# bluenumi.net
KiCad netlist of a schematic drawn in EAGLE
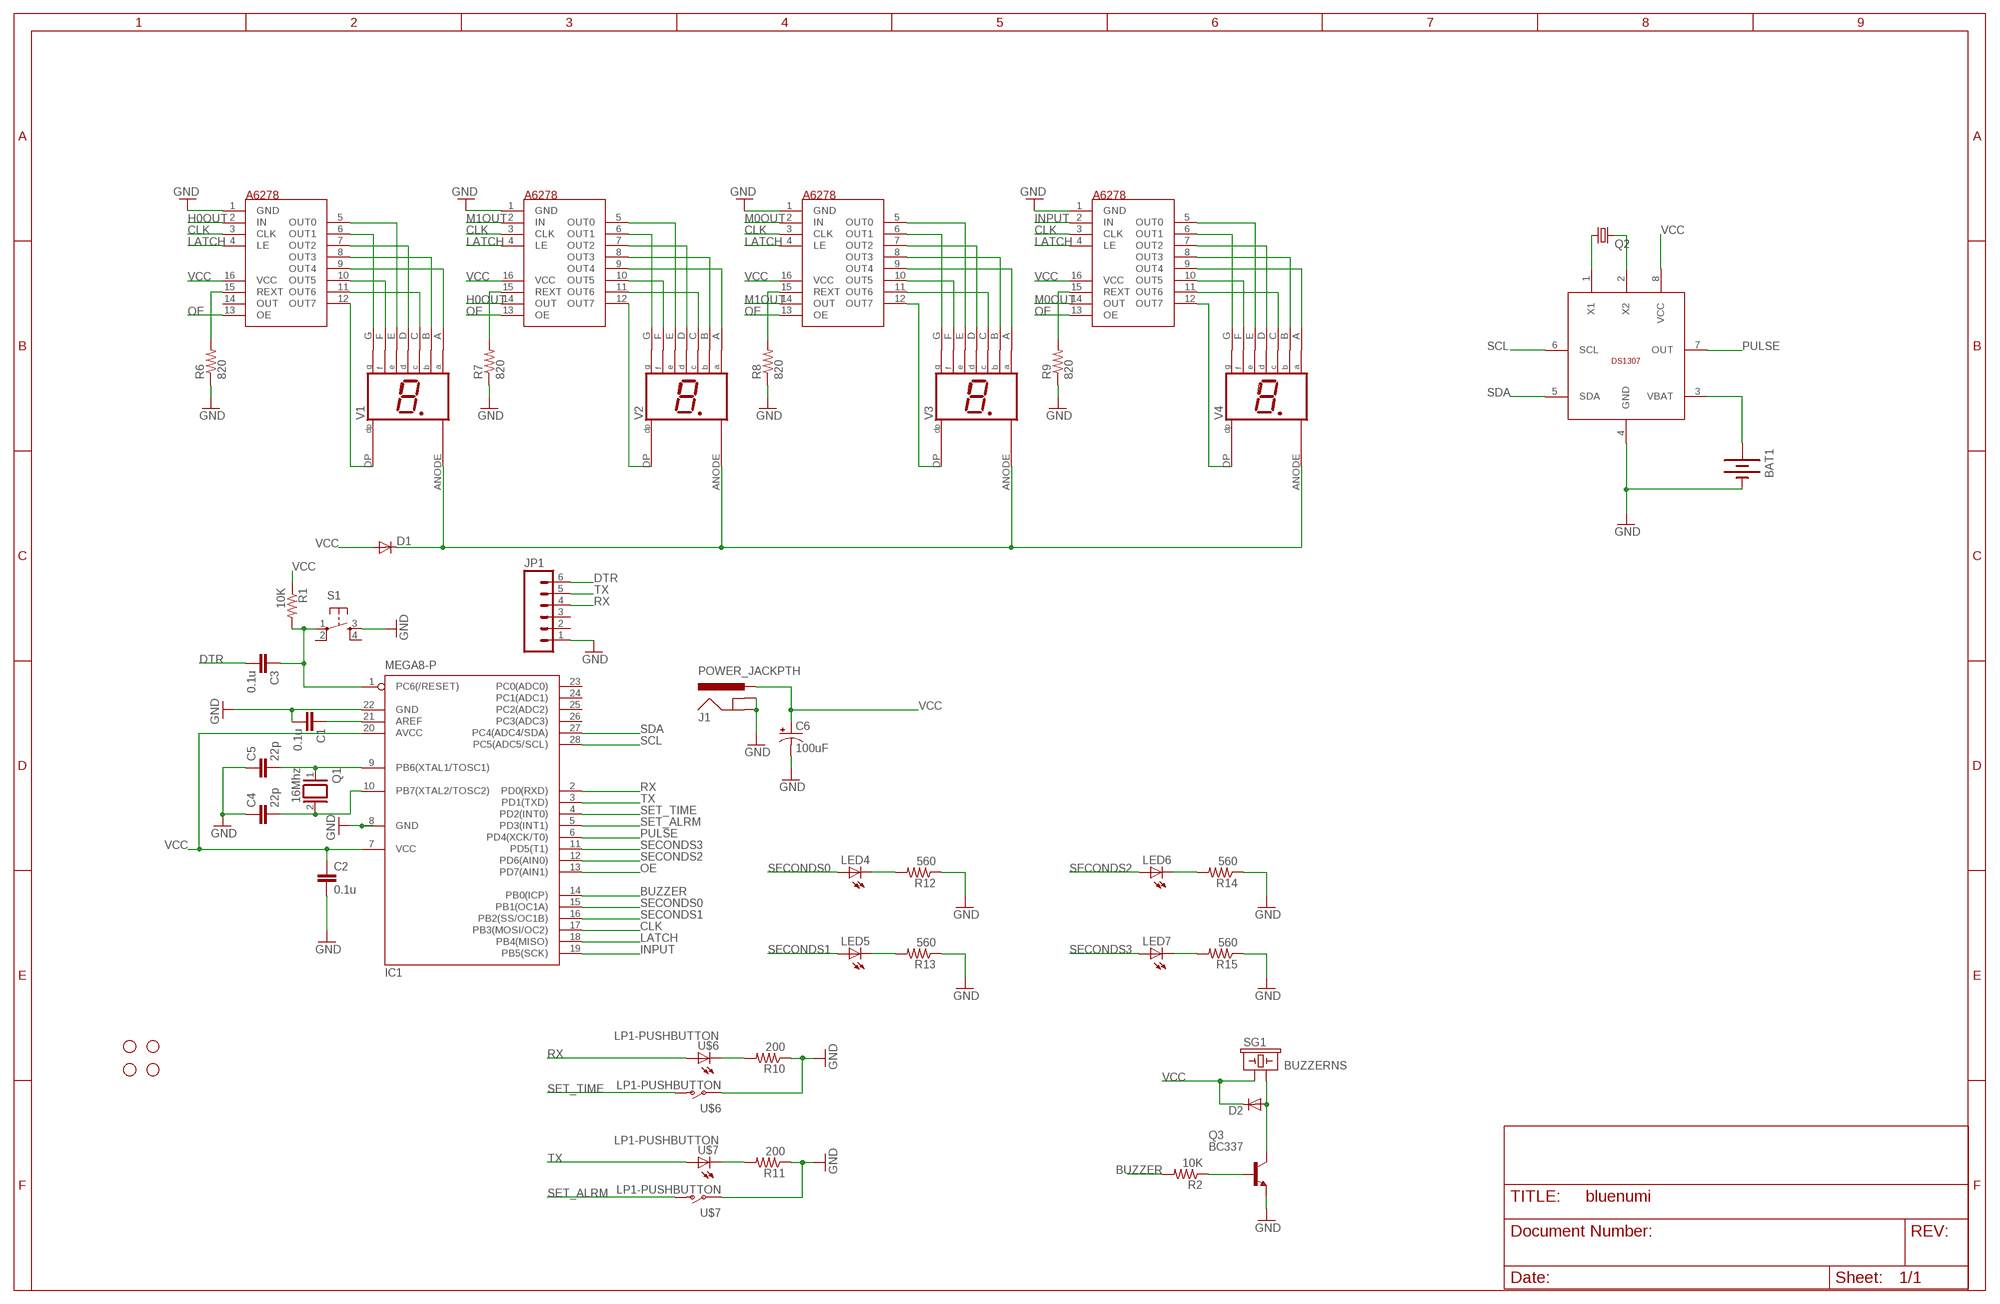
[diagram p0: schematic, sheet 1]

(export (version "E")
  (design (tool "Eeschema 10.0.6"))
  (components
    (comp (ref "BAT1")
      (value "BATTERY20PTH")
      (footprint "eagle-import:BATTCOM_20MM_PTH")
      (libsource (lib "eagle-import") (part "BATTERY20PTH"))
    )
    (comp (ref "C1")
      (value "0.1u")
      (footprint "eagle-import:CAP-PTH-SMALL")
      (libsource (lib "eagle-import") (part "CAPPTH"))
    )
    (comp (ref "C2")
      (value "0.1u")
      (footprint "eagle-import:CAP-PTH-SMALL")
      (libsource (lib "eagle-import") (part "CAPPTH"))
    )
    (comp (ref "C3")
      (value "0.1u")
      (footprint "eagle-import:CAP-PTH-SMALL")
      (libsource (lib "eagle-import") (part "CAPPTH"))
    )
    (comp (ref "C4")
      (value "22p")
      (footprint "eagle-import:CAP-PTH-SMALL")
      (libsource (lib "eagle-import") (part "CAPPTH"))
    )
    (comp (ref "C5")
      (value "22p")
      (footprint "eagle-import:CAP-PTH-SMALL")
      (libsource (lib "eagle-import") (part "CAPPTH"))
    )
    (comp (ref "C6")
      (value "100uF")
      (footprint "eagle-import:CPOL-RADIAL-10UF-25V")
      (libsource (lib "eagle-import") (part "CAP_POLPTH2"))
    )
    (comp (ref "D1")
      (value "DIODEPTH")
      (footprint "eagle-import:DIODE-1N4001")
      (libsource (lib "eagle-import") (part "DIODEPTH"))
    )
    (comp (ref "D2")
      (value "DIODEPTH")
      (footprint "eagle-import:DIODE-1N4001")
      (libsource (lib "eagle-import") (part "DIODEPTH"))
    )
    (comp (ref "IC1")
      (value "MEGA8-P")
      (footprint "eagle-import:DIL28-3")
      (libsource (lib "eagle-import") (part "MEGA8-P"))
    )
    (comp (ref "J1")
      (value "POWER_JACKPTH")
      (footprint "eagle-import:POWER_JACK_PTH")
      (libsource (lib "eagle-import") (part "POWER_JACKPTH"))
    )
    (comp (ref "JP1")
      (value "M06LOCK")
      (footprint "eagle-import:1X06_LOCK")
      (libsource (lib "eagle-import") (part "M06LOCK"))
    )
    (comp (ref "LED4")
      (value "LED5MM")
      (footprint "eagle-import:LED5MM")
      (libsource (lib "eagle-import") (part "LED5MM"))
    )
    (comp (ref "LED5")
      (value "LED5MM")
      (footprint "eagle-import:LED5MM")
      (libsource (lib "eagle-import") (part "LED5MM"))
    )
    (comp (ref "LED6")
      (value "LED5MM")
      (footprint "eagle-import:LED5MM")
      (libsource (lib "eagle-import") (part "LED5MM"))
    )
    (comp (ref "LED7")
      (value "LED5MM")
      (footprint "eagle-import:LED5MM")
      (libsource (lib "eagle-import") (part "LED5MM"))
    )
    (comp (ref "Q1")
      (value "16Mhz")
      (footprint "eagle-import:QS")
      (libsource (lib "eagle-import") (part "XTAL/S"))
    )
    (comp (ref "Q2")
      (value "CRYSTALTC26H")
      (footprint "eagle-import:TC26H")
      (libsource (lib "eagle-import") (part "CRYSTALTC26H"))
    )
    (comp (ref "Q3")
      (value "BC337")
      (footprint "eagle-import:TO92")
      (libsource (lib "eagle-import") (part "BC337"))
    )
    (comp (ref "R1")
      (value "10K")
      (footprint "eagle-import:AXIAL-0.3")
      (libsource (lib "eagle-import") (part "RESISTORPTH1"))
    )
    (comp (ref "R2")
      (value "10K")
      (footprint "eagle-import:AXIAL-0.3")
      (libsource (lib "eagle-import") (part "RESISTORPTH1"))
    )
    (comp (ref "R6")
      (value "820")
      (footprint "eagle-import:AXIAL-0.3")
      (libsource (lib "eagle-import") (part "RESISTORPTH1"))
    )
    (comp (ref "R7")
      (value "820")
      (footprint "eagle-import:AXIAL-0.3")
      (libsource (lib "eagle-import") (part "RESISTORPTH1"))
    )
    (comp (ref "R8")
      (value "820")
      (footprint "eagle-import:AXIAL-0.3")
      (libsource (lib "eagle-import") (part "RESISTORPTH1"))
    )
    (comp (ref "R9")
      (value "820")
      (footprint "eagle-import:AXIAL-0.3")
      (libsource (lib "eagle-import") (part "RESISTORPTH1"))
    )
    (comp (ref "R10")
      (value "200")
      (footprint "eagle-import:AXIAL-0.3")
      (libsource (lib "eagle-import") (part "RESISTORPTH1"))
    )
    (comp (ref "R11")
      (value "200")
      (footprint "eagle-import:AXIAL-0.3")
      (libsource (lib "eagle-import") (part "RESISTORPTH1"))
    )
    (comp (ref "R12")
      (value "560")
      (footprint "eagle-import:AXIAL-0.3")
      (libsource (lib "eagle-import") (part "RESISTORPTH1"))
    )
    (comp (ref "R13")
      (value "560")
      (footprint "eagle-import:AXIAL-0.3")
      (libsource (lib "eagle-import") (part "RESISTORPTH1"))
    )
    (comp (ref "R14")
      (value "560")
      (footprint "eagle-import:AXIAL-0.3")
      (libsource (lib "eagle-import") (part "RESISTORPTH1"))
    )
    (comp (ref "R15")
      (value "560")
      (footprint "eagle-import:AXIAL-0.3")
      (libsource (lib "eagle-import") (part "RESISTORPTH1"))
    )
    (comp (ref "S1")
      (value "TAC_SWITCHPTH")
      (footprint "eagle-import:TACTILE-PTH")
      (libsource (lib "eagle-import") (part "TAC_SWITCHPTH"))
    )
    (comp (ref "SG1")
      (value "BUZZERNS")
      (footprint "eagle-import:BUZZER-12MM-NS")
      (libsource (lib "eagle-import") (part "BUZZERNS"))
    )
    (comp (ref "U$1")
      (value "TLC5916")
      (footprint "eagle-import:DIL16")
      (libsource (lib "eagle-import") (part "A6278EAT"))
    )
    (comp (ref "U$2")
      (value "A6278EAT")
      (footprint "eagle-import:DIL16")
      (libsource (lib "eagle-import") (part "A6278EAT"))
    )
    (comp (ref "U$3")
      (value "A6278EAT")
      (footprint "eagle-import:DIL16")
      (libsource (lib "eagle-import") (part "A6278EAT"))
    )
    (comp (ref "U$4")
      (value "A6278EAT")
      (footprint "eagle-import:DIL16")
      (libsource (lib "eagle-import") (part "A6278EAT"))
    )
    (comp (ref "U$5")
      (value "DS1307")
      (footprint "eagle-import:DIL08")
      (libsource (lib "eagle-import") (part "DS1307"))
    )
    (comp (ref "U$6")
      (value "LP1-PUSHBUTTON")
      (footprint "eagle-import:LP1-PUSHBUTTON")
      (libsource (lib "eagle-import") (part "LP1-PUSHBUTTON"))
    )
    (comp (ref "U$7")
      (value "LP1-PUSHBUTTON")
      (footprint "eagle-import:LP1-PUSHBUTTON")
      (libsource (lib "eagle-import") (part "LP1-PUSHBUTTON"))
    )
    (comp (ref "U$8")
      (value "STAND-OFF")
      (footprint "eagle-import:STAND-OFF")
      (libsource (lib "eagle-import") (part "STAND-OFF"))
    )
    (comp (ref "U$9")
      (value "STAND-OFF")
      (footprint "eagle-import:STAND-OFF")
      (libsource (lib "eagle-import") (part "STAND-OFF"))
    )
    (comp (ref "U$10")
      (value "STAND-OFF")
      (footprint "eagle-import:STAND-OFF")
      (libsource (lib "eagle-import") (part "STAND-OFF"))
    )
    (comp (ref "U$11")
      (value "STAND-OFF")
      (footprint "eagle-import:STAND-OFF")
      (libsource (lib "eagle-import") (part "STAND-OFF"))
    )
    (comp (ref "V1")
      (value "IV-9-UNDERLIT")
      (footprint "eagle-import:9PINTUBE-WIDE")
      (libsource (lib "eagle-import") (part "IV-9-UNDERLIT"))
    )
    (comp (ref "V2")
      (value "IV-9-UNDERLIT")
      (footprint "eagle-import:9PINTUBE-WIDE")
      (libsource (lib "eagle-import") (part "IV-9-UNDERLIT"))
    )
    (comp (ref "V3")
      (value "IV-9-UNDERLIT")
      (footprint "eagle-import:9PINTUBE-WIDE")
      (libsource (lib "eagle-import") (part "IV-9-UNDERLIT"))
    )
    (comp (ref "V4")
      (value "IV-9-UNDERLIT")
      (footprint "eagle-import:9PINTUBE-WIDE")
      (libsource (lib "eagle-import") (part "IV-9-UNDERLIT"))
    )
  )
  (nets
    (net (code "1") (name "/BUZZER") (class "Default")
      (node (ref "IC1") (pin "14") (pinfunction "PB0(ICP)_14") (pintype "bidirectional"))
      (node (ref "R2") (pin "P$2") (pinfunction "2_P$2") (pintype "passive"))
    )
    (net (code "2") (name "/CLK") (class "Default")
      (node (ref "IC1") (pin "17") (pinfunction "PB3(MOSI/OC2)_17") (pintype "bidirectional"))
      (node (ref "U$1") (pin "3") (pinfunction "CLK_3") (pintype "bidirectional"))
      (node (ref "U$2") (pin "3") (pinfunction "CLK_3") (pintype "bidirectional"))
      (node (ref "U$3") (pin "3") (pinfunction "CLK_3") (pintype "bidirectional"))
      (node (ref "U$4") (pin "3") (pinfunction "CLK_3") (pintype "bidirectional"))
    )
    (net (code "3") (name "/DTR") (class "Default")
      (node (ref "C3") (pin "2") (pinfunction "2_2") (pintype "passive"))
      (node (ref "JP1") (pin "6") (pinfunction "6_6") (pintype "passive"))
    )
    (net (code "4") (name "/H0OUT") (class "Default")
      (node (ref "U$1") (pin "2") (pinfunction "IN_2") (pintype "bidirectional"))
      (node (ref "U$2") (pin "14") (pinfunction "OUT_14") (pintype "bidirectional"))
    )
    (net (code "5") (name "/INPUT") (class "Default")
      (node (ref "IC1") (pin "19") (pinfunction "PB5(SCK)_19") (pintype "bidirectional"))
      (node (ref "U$4") (pin "2") (pinfunction "IN_2") (pintype "bidirectional"))
    )
    (net (code "6") (name "/LATCH") (class "Default")
      (node (ref "IC1") (pin "18") (pinfunction "PB4(MISO)_18") (pintype "bidirectional"))
      (node (ref "U$1") (pin "4") (pinfunction "LE_4") (pintype "bidirectional"))
      (node (ref "U$2") (pin "4") (pinfunction "LE_4") (pintype "bidirectional"))
      (node (ref "U$3") (pin "4") (pinfunction "LE_4") (pintype "bidirectional"))
      (node (ref "U$4") (pin "4") (pinfunction "LE_4") (pintype "bidirectional"))
    )
    (net (code "7") (name "/M0OUT") (class "Default")
      (node (ref "U$3") (pin "2") (pinfunction "IN_2") (pintype "bidirectional"))
      (node (ref "U$4") (pin "14") (pinfunction "OUT_14") (pintype "bidirectional"))
    )
    (net (code "8") (name "/M1OUT") (class "Default")
      (node (ref "U$2") (pin "2") (pinfunction "IN_2") (pintype "bidirectional"))
      (node (ref "U$3") (pin "14") (pinfunction "OUT_14") (pintype "bidirectional"))
    )
    (net (code "9") (name "/OE") (class "Default")
      (node (ref "IC1") (pin "13") (pinfunction "PD7(AIN1)_13") (pintype "bidirectional"))
      (node (ref "U$1") (pin "13") (pinfunction "OE_13") (pintype "bidirectional"))
      (node (ref "U$2") (pin "13") (pinfunction "OE_13") (pintype "bidirectional"))
      (node (ref "U$3") (pin "13") (pinfunction "OE_13") (pintype "bidirectional"))
      (node (ref "U$4") (pin "13") (pinfunction "OE_13") (pintype "bidirectional"))
    )
    (net (code "10") (name "/PULSE") (class "Default")
      (node (ref "IC1") (pin "6") (pinfunction "PD4(XCK/T0)_6") (pintype "bidirectional"))
      (node (ref "U$5") (pin "7") (pinfunction "OUT_7") (pintype "bidirectional"))
    )
    (net (code "11") (name "/RX") (class "Default")
      (node (ref "IC1") (pin "2") (pinfunction "PD0(RXD)_2") (pintype "bidirectional"))
      (node (ref "JP1") (pin "4") (pinfunction "4_4") (pintype "passive"))
      (node (ref "U$6") (pin "ANODE") (pinfunction "ANODE_ANODE") (pintype "passive"))
    )
    (net (code "12") (name "/SCL") (class "Default")
      (node (ref "IC1") (pin "28") (pinfunction "PC5(ADC5/SCL)_28") (pintype "bidirectional"))
      (node (ref "U$5") (pin "6") (pinfunction "SCL_6") (pintype "bidirectional"))
    )
    (net (code "13") (name "/SDA") (class "Default")
      (node (ref "IC1") (pin "27") (pinfunction "PC4(ADC4/SDA)_27") (pintype "bidirectional"))
      (node (ref "U$5") (pin "5") (pinfunction "SDA_5") (pintype "bidirectional"))
    )
    (net (code "14") (name "/SECONDS0") (class "Default")
      (node (ref "IC1") (pin "15") (pinfunction "PB1(OC1A)_15") (pintype "bidirectional"))
      (node (ref "LED4") (pin "A") (pinfunction "A_A") (pintype "passive"))
    )
    (net (code "15") (name "/SECONDS1") (class "Default")
      (node (ref "IC1") (pin "16") (pinfunction "PB2(SS/OC1B)_16") (pintype "bidirectional"))
      (node (ref "LED5") (pin "A") (pinfunction "A_A") (pintype "passive"))
    )
    (net (code "16") (name "/SECONDS2") (class "Default")
      (node (ref "IC1") (pin "12") (pinfunction "PD6(AIN0)_12") (pintype "bidirectional"))
      (node (ref "LED6") (pin "A") (pinfunction "A_A") (pintype "passive"))
    )
    (net (code "17") (name "/SECONDS3") (class "Default")
      (node (ref "IC1") (pin "11") (pinfunction "PD5(T1)_11") (pintype "bidirectional"))
      (node (ref "LED7") (pin "A") (pinfunction "A_A") (pintype "passive"))
    )
    (net (code "18") (name "/SET_ALRM") (class "Default")
      (node (ref "IC1") (pin "5") (pinfunction "PD3(INT1)_5") (pintype "bidirectional"))
      (node (ref "U$7") (pin "S1") (pinfunction "S1_S1") (pintype "passive"))
    )
    (net (code "19") (name "/SET_TIME") (class "Default")
      (node (ref "IC1") (pin "4") (pinfunction "PD2(INT0)_4") (pintype "bidirectional"))
      (node (ref "U$6") (pin "S1") (pinfunction "S1_S1") (pintype "passive"))
    )
    (net (code "20") (name "/TX") (class "Default")
      (node (ref "IC1") (pin "3") (pinfunction "PD1(TXD)_3") (pintype "bidirectional"))
      (node (ref "JP1") (pin "5") (pinfunction "5_5") (pintype "passive"))
      (node (ref "U$7") (pin "ANODE") (pinfunction "ANODE_ANODE") (pintype "passive"))
    )
    (net (code "21") (name "/VCC") (class "Default")
      (node (ref "C2") (pin "1") (pinfunction "1_1") (pintype "passive"))
      (node (ref "C6") (pin "1") (pinfunction "+_1") (pintype "passive"))
      (node (ref "D1") (pin "A") (pinfunction "A_A") (pintype "passive"))
      (node (ref "D2") (pin "C") (pinfunction "C_C") (pintype "passive"))
      (node (ref "IC1") (pin "20") (pinfunction "AVCC_20") (pintype "power_in"))
      (node (ref "IC1") (pin "7") (pinfunction "VCC_7") (pintype "power_in"))
      (node (ref "J1") (pin "PWR") (pinfunction "PWR_PWR") (pintype "bidirectional"))
      (node (ref "R1") (pin "P$1") (pinfunction "1_P$1") (pintype "passive"))
      (node (ref "SG1") (pin "+") (pinfunction "1_+") (pintype "passive"))
      (node (ref "U$1") (pin "16") (pinfunction "VCC_16") (pintype "bidirectional"))
      (node (ref "U$2") (pin "16") (pinfunction "VCC_16") (pintype "bidirectional"))
      (node (ref "U$3") (pin "16") (pinfunction "VCC_16") (pintype "bidirectional"))
      (node (ref "U$4") (pin "16") (pinfunction "VCC_16") (pintype "bidirectional"))
      (node (ref "U$5") (pin "8") (pinfunction "VCC_8") (pintype "bidirectional"))
    )
    (net (code "22") (name "GND") (class "Default")
      (node (ref "BAT1") (pin "2") (pinfunction "-_2") (pintype "power_in"))
      (node (ref "C1") (pin "2") (pinfunction "2_2") (pintype "passive"))
      (node (ref "C2") (pin "2") (pinfunction "2_2") (pintype "passive"))
      (node (ref "C4") (pin "1") (pinfunction "1_1") (pintype "passive"))
      (node (ref "C5") (pin "1") (pinfunction "1_1") (pintype "passive"))
      (node (ref "C6") (pin "2") (pinfunction "-_2") (pintype "passive"))
      (node (ref "IC1") (pin "22") (pinfunction "GND_22") (pintype "power_in"))
      (node (ref "IC1") (pin "8") (pinfunction "GND_8") (pintype "power_in"))
      (node (ref "J1") (pin "GND") (pinfunction "GND_GND") (pintype "bidirectional"))
      (node (ref "J1") (pin "GNDBREAK") (pinfunction "GNDBREAK_GNDBREAK") (pintype "bidirectional"))
      (node (ref "JP1") (pin "1") (pinfunction "1_1") (pintype "passive"))
      (node (ref "Q3") (pin "1") (pinfunction "E_1") (pintype "passive"))
      (node (ref "R10") (pin "P$1") (pinfunction "1_P$1") (pintype "passive"))
      (node (ref "R11") (pin "P$1") (pinfunction "1_P$1") (pintype "passive"))
      (node (ref "R12") (pin "P$1") (pinfunction "1_P$1") (pintype "passive"))
      (node (ref "R13") (pin "P$1") (pinfunction "1_P$1") (pintype "passive"))
      (node (ref "R14") (pin "P$1") (pinfunction "1_P$1") (pintype "passive"))
      (node (ref "R15") (pin "P$1") (pinfunction "1_P$1") (pintype "passive"))
      (node (ref "R6") (pin "P$1") (pinfunction "1_P$1") (pintype "passive"))
      (node (ref "R7") (pin "P$1") (pinfunction "1_P$1") (pintype "passive"))
      (node (ref "R8") (pin "P$1") (pinfunction "1_P$1") (pintype "passive"))
      (node (ref "R9") (pin "P$1") (pinfunction "1_P$1") (pintype "passive"))
      (node (ref "S1") (pin "3") (pinfunction "3_3") (pintype "passive"))
      (node (ref "U$1") (pin "1") (pinfunction "GND_1") (pintype "bidirectional"))
      (node (ref "U$2") (pin "1") (pinfunction "GND_1") (pintype "bidirectional"))
      (node (ref "U$3") (pin "1") (pinfunction "GND_1") (pintype "bidirectional"))
      (node (ref "U$4") (pin "1") (pinfunction "GND_1") (pintype "bidirectional"))
      (node (ref "U$5") (pin "4") (pinfunction "GND_4") (pintype "bidirectional"))
      (node (ref "U$6") (pin "S2") (pinfunction "S2_S2") (pintype "passive"))
      (node (ref "U$7") (pin "S2") (pinfunction "S2_S2") (pintype "passive"))
    )
    (net (code "23") (name "Net-(BAT1-+)") (class "Default")
      (node (ref "BAT1") (pin "1") (pinfunction "+_1") (pintype "power_in"))
      (node (ref "U$5") (pin "3") (pinfunction "VBAT_3") (pintype "bidirectional"))
    )
    (net (code "24") (name "Net-(D1-PadC)") (class "Default")
      (node (ref "D1") (pin "C") (pinfunction "C_C") (pintype "passive"))
      (node (ref "V1") (pin "ANODE") (pinfunction "ANODE_ANODE") (pintype "passive"))
      (node (ref "V2") (pin "ANODE") (pinfunction "ANODE_ANODE") (pintype "passive"))
      (node (ref "V3") (pin "ANODE") (pinfunction "ANODE_ANODE") (pintype "passive"))
      (node (ref "V4") (pin "ANODE") (pinfunction "ANODE_ANODE") (pintype "passive"))
    )
    (net (code "25") (name "Net-(IC1-AREF)") (class "Default")
      (node (ref "C1") (pin "1") (pinfunction "1_1") (pintype "passive"))
      (node (ref "IC1") (pin "21") (pinfunction "AREF_21") (pintype "passive"))
    )
    (net (code "26") (name "Net-(IC1-PB6(XTAL1{slash}TOSC1))") (class "Default")
      (node (ref "C5") (pin "2") (pinfunction "2_2") (pintype "passive"))
      (node (ref "IC1") (pin "9") (pinfunction "PB6(XTAL1/TOSC1)_9") (pintype "bidirectional"))
      (node (ref "Q1") (pin "1") (pinfunction "1_1") (pintype "passive"))
    )
    (net (code "27") (name "Net-(IC1-PB7(XTAL2{slash}TOSC2))") (class "Default")
      (node (ref "C4") (pin "2") (pinfunction "2_2") (pintype "passive"))
      (node (ref "IC1") (pin "10") (pinfunction "PB7(XTAL2/TOSC2)_10") (pintype "bidirectional"))
      (node (ref "Q1") (pin "2") (pinfunction "2_2") (pintype "passive"))
    )
    (net (code "28") (name "Net-(IC1-PC6({slash}RESET))") (class "Default")
      (node (ref "C3") (pin "1") (pinfunction "1_1") (pintype "passive"))
      (node (ref "IC1") (pin "1") (pinfunction "PC6(/RESET)_1") (pintype "bidirectional"))
      (node (ref "R1") (pin "P$2") (pinfunction "2_P$2") (pintype "passive"))
      (node (ref "S1") (pin "1") (pinfunction "1_1") (pintype "passive"))
    )
    (net (code "29") (name "Net-(LED4-C)") (class "Default")
      (node (ref "LED4") (pin "K") (pinfunction "C_K") (pintype "passive"))
      (node (ref "R12") (pin "P$2") (pinfunction "2_P$2") (pintype "passive"))
    )
    (net (code "30") (name "Net-(LED5-C)") (class "Default")
      (node (ref "LED5") (pin "K") (pinfunction "C_K") (pintype "passive"))
      (node (ref "R13") (pin "P$2") (pinfunction "2_P$2") (pintype "passive"))
    )
    (net (code "31") (name "Net-(LED6-C)") (class "Default")
      (node (ref "LED6") (pin "K") (pinfunction "C_K") (pintype "passive"))
      (node (ref "R14") (pin "P$2") (pinfunction "2_P$2") (pintype "passive"))
    )
    (net (code "32") (name "Net-(LED7-C)") (class "Default")
      (node (ref "LED7") (pin "K") (pinfunction "C_K") (pintype "passive"))
      (node (ref "R15") (pin "P$2") (pinfunction "2_P$2") (pintype "passive"))
    )
    (net (code "33") (name "Net-(Q3-B)") (class "Default")
      (node (ref "Q3") (pin "2") (pinfunction "B_2") (pintype "passive"))
      (node (ref "R2") (pin "P$1") (pinfunction "1_P$1") (pintype "passive"))
    )
    (net (code "34") (name "Net-(Q3-C)") (class "Default")
      (node (ref "D2") (pin "A") (pinfunction "A_A") (pintype "passive"))
      (node (ref "Q3") (pin "3") (pinfunction "C_3") (pintype "passive"))
      (node (ref "SG1") (pin "-") (pinfunction "2_-") (pintype "passive"))
    )
    (net (code "35") (name "Net-(R6-2)") (class "Default")
      (node (ref "R6") (pin "P$2") (pinfunction "2_P$2") (pintype "passive"))
      (node (ref "U$1") (pin "15") (pinfunction "REXT_15") (pintype "bidirectional"))
    )
    (net (code "36") (name "Net-(R7-2)") (class "Default")
      (node (ref "R7") (pin "P$2") (pinfunction "2_P$2") (pintype "passive"))
      (node (ref "U$2") (pin "15") (pinfunction "REXT_15") (pintype "bidirectional"))
    )
    (net (code "37") (name "Net-(R8-2)") (class "Default")
      (node (ref "R8") (pin "P$2") (pinfunction "2_P$2") (pintype "passive"))
      (node (ref "U$3") (pin "15") (pinfunction "REXT_15") (pintype "bidirectional"))
    )
    (net (code "38") (name "Net-(R9-2)") (class "Default")
      (node (ref "R9") (pin "P$2") (pinfunction "2_P$2") (pintype "passive"))
      (node (ref "U$4") (pin "15") (pinfunction "REXT_15") (pintype "bidirectional"))
    )
    (net (code "39") (name "Net-(R10-2)") (class "Default")
      (node (ref "R10") (pin "P$2") (pinfunction "2_P$2") (pintype "passive"))
      (node (ref "U$6") (pin "CATHODE") (pinfunction "CATHODE_CATHODE") (pintype "passive"))
    )
    (net (code "40") (name "Net-(R11-2)") (class "Default")
      (node (ref "R11") (pin "P$2") (pinfunction "2_P$2") (pintype "passive"))
      (node (ref "U$7") (pin "CATHODE") (pinfunction "CATHODE_CATHODE") (pintype "passive"))
    )
    (net (code "41") (name "Net-(U$1-OUT0)") (class "Default")
      (node (ref "U$1") (pin "5") (pinfunction "OUT0_5") (pintype "bidirectional"))
      (node (ref "V1") (pin "E") (pinfunction "E_E") (pintype "passive"))
    )
    (net (code "42") (name "Net-(U$1-OUT1)") (class "Default")
      (node (ref "U$1") (pin "6") (pinfunction "OUT1_6") (pintype "bidirectional"))
      (node (ref "V1") (pin "G") (pinfunction "G_G") (pintype "passive"))
    )
    (net (code "43") (name "Net-(U$1-OUT2)") (class "Default")
      (node (ref "U$1") (pin "7") (pinfunction "OUT2_7") (pintype "bidirectional"))
      (node (ref "V1") (pin "D") (pinfunction "D_D") (pintype "passive"))
    )
    (net (code "44") (name "Net-(U$1-OUT3)") (class "Default")
      (node (ref "U$1") (pin "8") (pinfunction "OUT3_8") (pintype "bidirectional"))
      (node (ref "V1") (pin "B") (pinfunction "B_B") (pintype "passive"))
    )
    (net (code "45") (name "Net-(U$1-OUT4)") (class "Default")
      (node (ref "U$1") (pin "9") (pinfunction "OUT4_9") (pintype "bidirectional"))
      (node (ref "V1") (pin "A") (pinfunction "A_A") (pintype "passive"))
    )
    (net (code "46") (name "Net-(U$1-OUT5)") (class "Default")
      (node (ref "U$1") (pin "10") (pinfunction "OUT5_10") (pintype "bidirectional"))
      (node (ref "V1") (pin "F") (pinfunction "F_F") (pintype "passive"))
    )
    (net (code "47") (name "Net-(U$1-OUT6)") (class "Default")
      (node (ref "U$1") (pin "11") (pinfunction "OUT6_11") (pintype "bidirectional"))
      (node (ref "V1") (pin "C") (pinfunction "C_C") (pintype "passive"))
    )
    (net (code "48") (name "Net-(U$1-OUT7)") (class "Default")
      (node (ref "U$1") (pin "12") (pinfunction "OUT7_12") (pintype "bidirectional"))
      (node (ref "V1") (pin "DP") (pinfunction "DP_DP") (pintype "passive"))
    )
    (net (code "49") (name "Net-(U$2-OUT0)") (class "Default")
      (node (ref "U$2") (pin "5") (pinfunction "OUT0_5") (pintype "bidirectional"))
      (node (ref "V2") (pin "E") (pinfunction "E_E") (pintype "passive"))
    )
    (net (code "50") (name "Net-(U$2-OUT1)") (class "Default")
      (node (ref "U$2") (pin "6") (pinfunction "OUT1_6") (pintype "bidirectional"))
      (node (ref "V2") (pin "G") (pinfunction "G_G") (pintype "passive"))
    )
    (net (code "51") (name "Net-(U$2-OUT2)") (class "Default")
      (node (ref "U$2") (pin "7") (pinfunction "OUT2_7") (pintype "bidirectional"))
      (node (ref "V2") (pin "D") (pinfunction "D_D") (pintype "passive"))
    )
    (net (code "52") (name "Net-(U$2-OUT3)") (class "Default")
      (node (ref "U$2") (pin "8") (pinfunction "OUT3_8") (pintype "bidirectional"))
      (node (ref "V2") (pin "B") (pinfunction "B_B") (pintype "passive"))
    )
    (net (code "53") (name "Net-(U$2-OUT4)") (class "Default")
      (node (ref "U$2") (pin "9") (pinfunction "OUT4_9") (pintype "bidirectional"))
      (node (ref "V2") (pin "A") (pinfunction "A_A") (pintype "passive"))
    )
    (net (code "54") (name "Net-(U$2-OUT5)") (class "Default")
      (node (ref "U$2") (pin "10") (pinfunction "OUT5_10") (pintype "bidirectional"))
      (node (ref "V2") (pin "F") (pinfunction "F_F") (pintype "passive"))
    )
    (net (code "55") (name "Net-(U$2-OUT6)") (class "Default")
      (node (ref "U$2") (pin "11") (pinfunction "OUT6_11") (pintype "bidirectional"))
      (node (ref "V2") (pin "C") (pinfunction "C_C") (pintype "passive"))
    )
    (net (code "56") (name "Net-(U$2-OUT7)") (class "Default")
      (node (ref "U$2") (pin "12") (pinfunction "OUT7_12") (pintype "bidirectional"))
      (node (ref "V2") (pin "DP") (pinfunction "DP_DP") (pintype "passive"))
    )
    (net (code "57") (name "Net-(U$3-OUT0)") (class "Default")
      (node (ref "U$3") (pin "5") (pinfunction "OUT0_5") (pintype "bidirectional"))
      (node (ref "V3") (pin "E") (pinfunction "E_E") (pintype "passive"))
    )
    (net (code "58") (name "Net-(U$3-OUT1)") (class "Default")
      (node (ref "U$3") (pin "6") (pinfunction "OUT1_6") (pintype "bidirectional"))
      (node (ref "V3") (pin "G") (pinfunction "G_G") (pintype "passive"))
    )
    (net (code "59") (name "Net-(U$3-OUT2)") (class "Default")
      (node (ref "U$3") (pin "7") (pinfunction "OUT2_7") (pintype "bidirectional"))
      (node (ref "V3") (pin "D") (pinfunction "D_D") (pintype "passive"))
    )
    (net (code "60") (name "Net-(U$3-OUT3)") (class "Default")
      (node (ref "U$3") (pin "8") (pinfunction "OUT3_8") (pintype "bidirectional"))
      (node (ref "V3") (pin "B") (pinfunction "B_B") (pintype "passive"))
    )
    (net (code "61") (name "Net-(U$3-OUT4)") (class "Default")
      (node (ref "U$3") (pin "9") (pinfunction "OUT4_9") (pintype "bidirectional"))
      (node (ref "V3") (pin "A") (pinfunction "A_A") (pintype "passive"))
    )
    (net (code "62") (name "Net-(U$3-OUT5)") (class "Default")
      (node (ref "U$3") (pin "10") (pinfunction "OUT5_10") (pintype "bidirectional"))
      (node (ref "V3") (pin "F") (pinfunction "F_F") (pintype "passive"))
    )
    (net (code "63") (name "Net-(U$3-OUT6)") (class "Default")
      (node (ref "U$3") (pin "11") (pinfunction "OUT6_11") (pintype "bidirectional"))
      (node (ref "V3") (pin "C") (pinfunction "C_C") (pintype "passive"))
    )
    (net (code "64") (name "Net-(U$3-OUT7)") (class "Default")
      (node (ref "U$3") (pin "12") (pinfunction "OUT7_12") (pintype "bidirectional"))
      (node (ref "V3") (pin "DP") (pinfunction "DP_DP") (pintype "passive"))
    )
    (net (code "65") (name "Net-(U$4-OUT0)") (class "Default")
      (node (ref "U$4") (pin "5") (pinfunction "OUT0_5") (pintype "bidirectional"))
      (node (ref "V4") (pin "E") (pinfunction "E_E") (pintype "passive"))
    )
    (net (code "66") (name "Net-(U$4-OUT1)") (class "Default")
      (node (ref "U$4") (pin "6") (pinfunction "OUT1_6") (pintype "bidirectional"))
      (node (ref "V4") (pin "G") (pinfunction "G_G") (pintype "passive"))
    )
    (net (code "67") (name "Net-(U$4-OUT2)") (class "Default")
      (node (ref "U$4") (pin "7") (pinfunction "OUT2_7") (pintype "bidirectional"))
      (node (ref "V4") (pin "D") (pinfunction "D_D") (pintype "passive"))
    )
    (net (code "68") (name "Net-(U$4-OUT3)") (class "Default")
      (node (ref "U$4") (pin "8") (pinfunction "OUT3_8") (pintype "bidirectional"))
      (node (ref "V4") (pin "B") (pinfunction "B_B") (pintype "passive"))
    )
    (net (code "69") (name "Net-(U$4-OUT4)") (class "Default")
      (node (ref "U$4") (pin "9") (pinfunction "OUT4_9") (pintype "bidirectional"))
      (node (ref "V4") (pin "A") (pinfunction "A_A") (pintype "passive"))
    )
    (net (code "70") (name "Net-(U$4-OUT5)") (class "Default")
      (node (ref "U$4") (pin "10") (pinfunction "OUT5_10") (pintype "bidirectional"))
      (node (ref "V4") (pin "F") (pinfunction "F_F") (pintype "passive"))
    )
    (net (code "71") (name "Net-(U$4-OUT6)") (class "Default")
      (node (ref "U$4") (pin "11") (pinfunction "OUT6_11") (pintype "bidirectional"))
      (node (ref "V4") (pin "C") (pinfunction "C_C") (pintype "passive"))
    )
    (net (code "72") (name "Net-(U$4-OUT7)") (class "Default")
      (node (ref "U$4") (pin "12") (pinfunction "OUT7_12") (pintype "bidirectional"))
      (node (ref "V4") (pin "DP") (pinfunction "DP_DP") (pintype "passive"))
    )
    (net (code "73") (name "Net-(U$5-X1)") (class "Default")
      (node (ref "Q2") (pin "1") (pinfunction "1_1") (pintype "passive"))
      (node (ref "U$5") (pin "1") (pinfunction "X1_1") (pintype "bidirectional"))
    )
    (net (code "74") (name "Net-(U$5-X2)") (class "Default")
      (node (ref "Q2") (pin "2") (pinfunction "2_2") (pintype "passive"))
      (node (ref "U$5") (pin "2") (pinfunction "X2_2") (pintype "bidirectional"))
    )
    (net (code "75") (name "unconnected-(IC1-PC0(ADC0)-Pad23)") (class "Default")
      (node (ref "IC1") (pin "23") (pinfunction "PC0(ADC0)_23") (pintype "bidirectional"))
    )
    (net (code "76") (name "unconnected-(IC1-PC1(ADC1)-Pad24)") (class "Default")
      (node (ref "IC1") (pin "24") (pinfunction "PC1(ADC1)_24") (pintype "bidirectional"))
    )
    (net (code "77") (name "unconnected-(IC1-PC2(ADC2)-Pad25)") (class "Default")
      (node (ref "IC1") (pin "25") (pinfunction "PC2(ADC2)_25") (pintype "bidirectional"))
    )
    (net (code "78") (name "unconnected-(IC1-PC3(ADC3)-Pad26)") (class "Default")
      (node (ref "IC1") (pin "26") (pinfunction "PC3(ADC3)_26") (pintype "bidirectional"))
    )
    (net (code "79") (name "unconnected-(JP1-Pad2)") (class "Default")
      (node (ref "JP1") (pin "2") (pinfunction "2_2") (pintype "passive"))
    )
    (net (code "80") (name "unconnected-(JP1-Pad3)") (class "Default")
      (node (ref "JP1") (pin "3") (pinfunction "3_3") (pintype "passive"))
    )
    (net (code "81") (name "unconnected-(S1-Pad2)") (class "Default")
      (node (ref "S1") (pin "2") (pinfunction "2_2") (pintype "passive"))
    )
    (net (code "82") (name "unconnected-(S1-Pad4)") (class "Default")
      (node (ref "S1") (pin "4") (pinfunction "4_4") (pintype "passive"))
    )
    (net (code "83") (name "unconnected-(U$1-OUT-Pad14)") (class "Default")
      (node (ref "U$1") (pin "14") (pinfunction "OUT_14") (pintype "bidirectional"))
    )
  )
)
